# wander-compass-upside-down.net
KiCad netlist of a schematic drawn in EAGLE
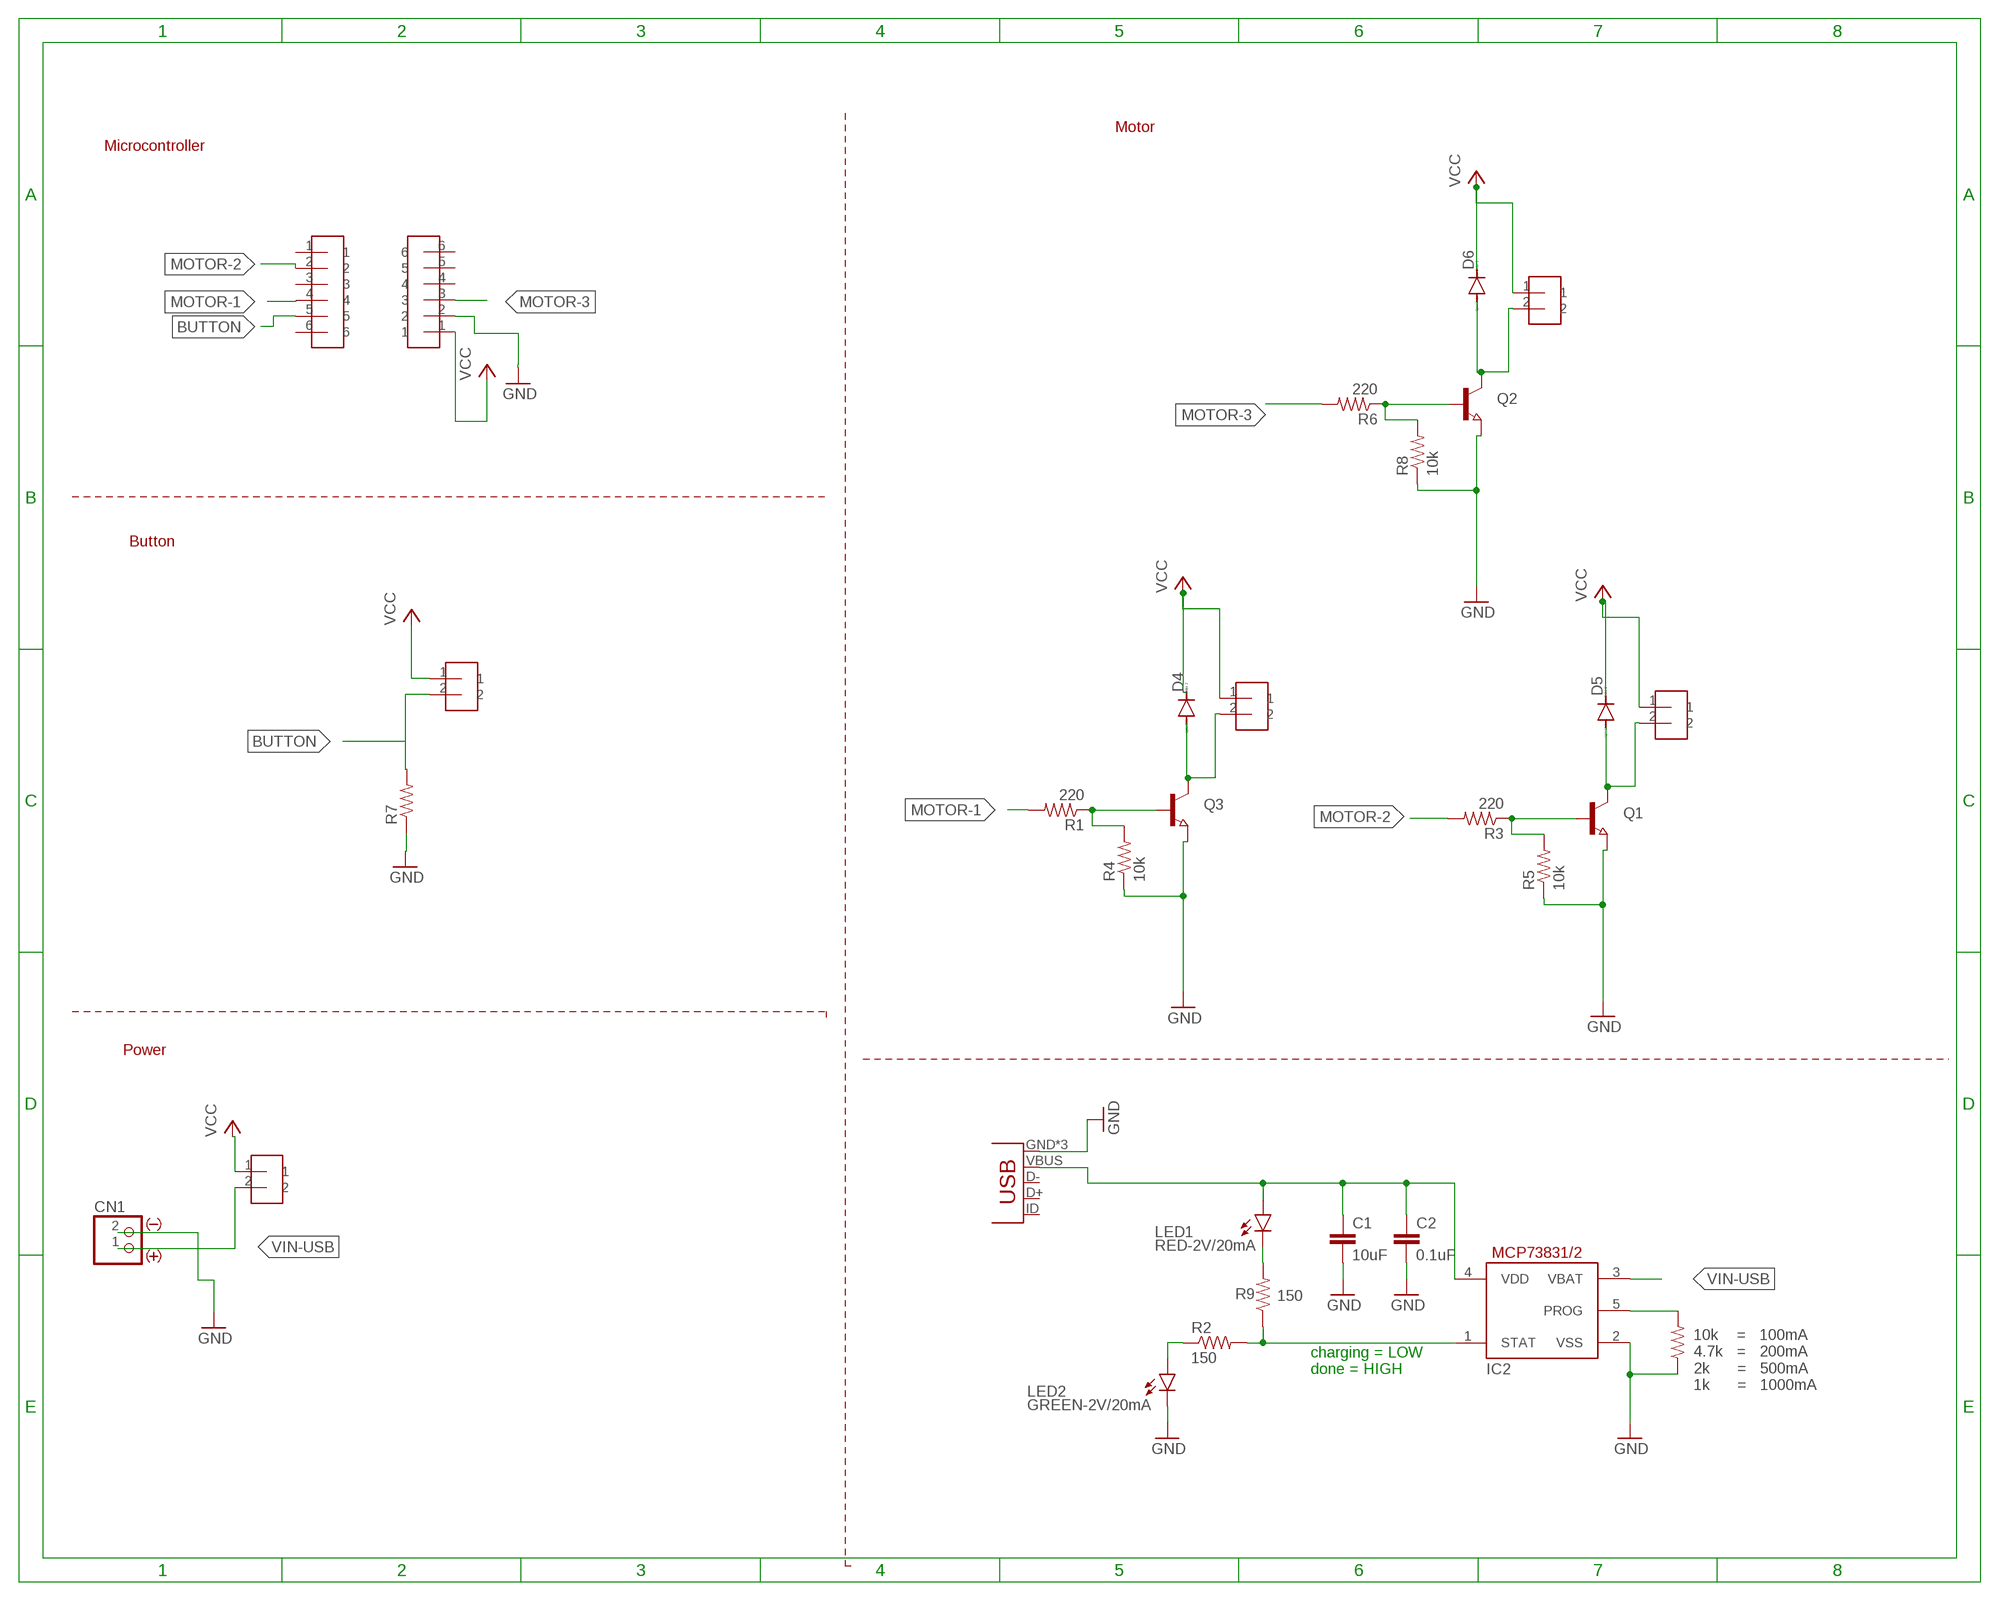
[diagram p0: schematic, sheet 1]

(export (version "E")
  (design (tool "Eeschema 10.0.6"))
  (components
    (comp (ref "C1")
      (value "10uF")
      (footprint "eagle-import:0805")
      (libsource (lib "eagle-import") (part "CAP-0805"))
    )
    (comp (ref "C2")
      (value "0.1uF")
      (footprint "eagle-import:0805")
      (libsource (lib "eagle-import") (part "CAP-0805"))
    )
    (comp (ref "CN1")
      (value "JST_2PIN_BATTERY-SMT-HORIZ")
      (footprint "eagle-import:JST-PH-2-SMT-RA")
      (libsource (lib "eagle-import") (part "JST_2PIN_BATTERY-SMT-HORIZ"))
    )
    (comp (ref "D4")
      (value "DIODE-SOD523")
      (footprint "eagle-import:SOD523")
      (libsource (lib "eagle-import") (part "DIODE-SOD523"))
    )
    (comp (ref "D5")
      (value "DIODE-SOD523")
      (footprint "eagle-import:SOD523")
      (libsource (lib "eagle-import") (part "DIODE-SOD523"))
    )
    (comp (ref "D6")
      (value "DIODE-SOD523")
      (footprint "eagle-import:SOD523")
      (libsource (lib "eagle-import") (part "DIODE-SOD523"))
    )
    (comp (ref "IC2")
      (value "LIPO_CHARGER/OT")
      (footprint "eagle-import:SOT23-5L")
      (libsource (lib "eagle-import") (part "LIPO_CHARGER/OT"))
    )
    (comp (ref "JP1")
      (value "USB_CONN-10118192-0001LF")
      (footprint "eagle-import:USB-MICROB")
      (libsource (lib "eagle-import") (part "USB_CONN-10118192-0001LF"))
    )
    (comp (ref "LED1")
      (value "RED-2V/20mA")
      (footprint "eagle-import:CHIP-LED0805")
      (libsource (lib "eagle-import") (part "LED-0805"))
    )
    (comp (ref "LED2")
      (value "GREEN-2V/20mA")
      (footprint "eagle-import:CHIP-LED0805")
      (libsource (lib "eagle-import") (part "LED-0805"))
    )
    (comp (ref "MOTOR-CENTER-HEADER")
      (value "HEADER-2")
      (footprint "eagle-import:HEADER-2")
      (libsource (lib "eagle-import") (part "HEADER-2"))
    )
    (comp (ref "MOTOR-RIGHT-HEADER")
      (value "HEADER-2")
      (footprint "eagle-import:HEADER-2")
      (libsource (lib "eagle-import") (part "HEADER-2"))
    )
    (comp (ref "MOTOR_LEFT_HEADER")
      (value "HEADER-2")
      (footprint "eagle-import:HEADER-2")
      (libsource (lib "eagle-import") (part "HEADER-2"))
    )
    (comp (ref "Q1")
      (value "TRANSISTOR-NPN-SOT23")
      (footprint "eagle-import:SOT23")
      (libsource (lib "eagle-import") (part "TRANSISTOR-NPN-SOT23"))
    )
    (comp (ref "Q2")
      (value "TRANSISTOR-NPN-SOT23")
      (footprint "eagle-import:SOT23")
      (libsource (lib "eagle-import") (part "TRANSISTOR-NPN-SOT23"))
    )
    (comp (ref "Q3")
      (value "TRANSISTOR-NPN-SOT23")
      (footprint "eagle-import:SOT23")
      (libsource (lib "eagle-import") (part "TRANSISTOR-NPN-SOT23"))
    )
    (comp (ref "R1")
      (value "220")
      (footprint "eagle-import:0603-RES")
      (libsource (lib "eagle-import") (part "RESISTOR0603"))
    )
    (comp (ref "R2")
      (value "150")
      (footprint "eagle-import:0805")
      (libsource (lib "eagle-import") (part "RESISTOR-0805"))
    )
    (comp (ref "R3")
      (value "220")
      (footprint "eagle-import:0603-RES")
      (libsource (lib "eagle-import") (part "RESISTOR0603"))
    )
    (comp (ref "R4")
      (value "10k")
      (footprint "eagle-import:0603-RES")
      (libsource (lib "eagle-import") (part "RESISTOR0603"))
    )
    (comp (ref "R5")
      (value "10k")
      (footprint "eagle-import:0603-RES")
      (libsource (lib "eagle-import") (part "RESISTOR0603"))
    )
    (comp (ref "R6")
      (value "220")
      (footprint "eagle-import:0603-RES")
      (libsource (lib "eagle-import") (part "RESISTOR0603"))
    )
    (comp (ref "R7")
      (value "RESISTOR0603")
      (footprint "eagle-import:0603-RES")
      (libsource (lib "eagle-import") (part "RESISTOR0603"))
    )
    (comp (ref "R8")
      (value "10k")
      (footprint "eagle-import:0603-RES")
      (libsource (lib "eagle-import") (part "RESISTOR0603"))
    )
    (comp (ref "R9")
      (value "150")
      (footprint "eagle-import:0805")
      (libsource (lib "eagle-import") (part "RESISTOR-0805"))
    )
    (comp (ref "R10")
      (value "2k")
      (footprint "eagle-import:0805")
      (libsource (lib "eagle-import") (part "RESISTOR-0805"))
    )
    (comp (ref "U$1")
      (value "HEADER-2")
      (footprint "eagle-import:HEADER-2")
      (libsource (lib "eagle-import") (part "HEADER-2"))
    )
    (comp (ref "U$5")
      (value "HEADER-6")
      (footprint "eagle-import:HEADER-6")
      (libsource (lib "eagle-import") (part "HEADER-6"))
    )
    (comp (ref "U$6")
      (value "HEADER-6")
      (footprint "eagle-import:HEADER-6")
      (libsource (lib "eagle-import") (part "HEADER-6"))
    )
    (comp (ref "U$7")
      (value "HEADER-2")
      (footprint "eagle-import:HEADER-2")
      (libsource (lib "eagle-import") (part "HEADER-2"))
    )
  )
  (nets
    (net (code "1") (name "BUTTON") (class "Default")
      (node (ref "R7") (pin "2") (pinfunction "2_2") (pintype "passive"))
      (node (ref "U$1") (pin "2") (pinfunction "2_2") (pintype "bidirectional"))
      (node (ref "U$6") (pin "5") (pinfunction "5_5") (pintype "bidirectional"))
    )
    (net (code "2") (name "GND") (class "Default")
      (node (ref "C1") (pin "2") (pinfunction "2_2") (pintype "passive"))
      (node (ref "C2") (pin "2") (pinfunction "2_2") (pintype "passive"))
      (node (ref "CN1") (pin "2") (pinfunction "1_2") (pintype "passive"))
      (node (ref "IC2") (pin "2") (pinfunction "VSS_2") (pintype "power_in"))
      (node (ref "JP1") (pin "GND") (pinfunction "GND_GND") (pintype "bidirectional"))
      (node (ref "JP1") (pin "MT1") (pinfunction "GND_MT1") (pintype "bidirectional"))
      (node (ref "JP1") (pin "MT2") (pinfunction "GND_MT2") (pintype "bidirectional"))
      (node (ref "LED2") (pin "C") (pinfunction "C_C") (pintype "passive"))
      (node (ref "Q1") (pin "2") (pinfunction "E_2") (pintype "passive"))
      (node (ref "Q2") (pin "2") (pinfunction "E_2") (pintype "passive"))
      (node (ref "Q3") (pin "2") (pinfunction "E_2") (pintype "passive"))
      (node (ref "R10") (pin "1") (pinfunction "1_1") (pintype "passive"))
      (node (ref "R4") (pin "1") (pinfunction "1_1") (pintype "passive"))
      (node (ref "R5") (pin "1") (pinfunction "1_1") (pintype "passive"))
      (node (ref "R7") (pin "1") (pinfunction "1_1") (pintype "passive"))
      (node (ref "R8") (pin "1") (pinfunction "1_1") (pintype "passive"))
      (node (ref "U$5") (pin "2") (pinfunction "2_2") (pintype "bidirectional"))
    )
    (net (code "3") (name "MOTOR-1") (class "Default")
      (node (ref "R1") (pin "2") (pinfunction "2_2") (pintype "passive"))
      (node (ref "U$6") (pin "4") (pinfunction "4_4") (pintype "bidirectional"))
    )
    (net (code "4") (name "MOTOR-2") (class "Default")
      (node (ref "R3") (pin "2") (pinfunction "2_2") (pintype "passive"))
      (node (ref "U$6") (pin "2") (pinfunction "2_2") (pintype "bidirectional"))
    )
    (net (code "5") (name "MOTOR-3") (class "Default")
      (node (ref "R6") (pin "2") (pinfunction "2_2") (pintype "passive"))
      (node (ref "U$5") (pin "3") (pinfunction "3_3") (pintype "bidirectional"))
    )
    (net (code "6") (name "Net-(IC2-PROG)") (class "Default")
      (node (ref "IC2") (pin "5") (pinfunction "PROG_5") (pintype "input"))
      (node (ref "R10") (pin "2") (pinfunction "2_2") (pintype "passive"))
    )
    (net (code "7") (name "Net-(IC2-STAT)") (class "Default")
      (node (ref "IC2") (pin "1") (pinfunction "STAT_1") (pintype "output"))
      (node (ref "R2") (pin "2") (pinfunction "2_2") (pintype "passive"))
      (node (ref "R9") (pin "1") (pinfunction "1_1") (pintype "passive"))
    )
    (net (code "8") (name "Net-(IC2-VDD)") (class "Default")
      (node (ref "C1") (pin "1") (pinfunction "1_1") (pintype "passive"))
      (node (ref "C2") (pin "1") (pinfunction "1_1") (pintype "passive"))
      (node (ref "IC2") (pin "4") (pinfunction "VDD_4") (pintype "power_in"))
      (node (ref "JP1") (pin "VBUS") (pinfunction "VBUS_VBUS") (pintype "bidirectional"))
      (node (ref "LED1") (pin "A") (pinfunction "A_A") (pintype "passive"))
    )
    (net (code "9") (name "Net-(LED1-PadC)") (class "Default")
      (node (ref "LED1") (pin "C") (pinfunction "C_C") (pintype "passive"))
      (node (ref "R9") (pin "2") (pinfunction "2_2") (pintype "passive"))
    )
    (net (code "10") (name "Net-(LED2-PadA)") (class "Default")
      (node (ref "LED2") (pin "A") (pinfunction "A_A") (pintype "passive"))
      (node (ref "R2") (pin "1") (pinfunction "1_1") (pintype "passive"))
    )
    (net (code "11") (name "Net-(Q1-B)") (class "Default")
      (node (ref "Q1") (pin "1") (pinfunction "B_1") (pintype "passive"))
      (node (ref "R3") (pin "1") (pinfunction "1_1") (pintype "passive"))
      (node (ref "R5") (pin "2") (pinfunction "2_2") (pintype "passive"))
    )
    (net (code "12") (name "Net-(Q1-C)") (class "Default")
      (node (ref "D5") (pin "A") (pinfunction "A_A") (pintype "passive"))
      (node (ref "MOTOR-CENTER-HEADER") (pin "2") (pinfunction "2_2") (pintype "bidirectional"))
      (node (ref "Q1") (pin "3") (pinfunction "C_3") (pintype "passive"))
    )
    (net (code "13") (name "Net-(Q2-B)") (class "Default")
      (node (ref "Q2") (pin "1") (pinfunction "B_1") (pintype "passive"))
      (node (ref "R6") (pin "1") (pinfunction "1_1") (pintype "passive"))
      (node (ref "R8") (pin "2") (pinfunction "2_2") (pintype "passive"))
    )
    (net (code "14") (name "Net-(Q2-C)") (class "Default")
      (node (ref "D6") (pin "A") (pinfunction "A_A") (pintype "passive"))
      (node (ref "MOTOR-RIGHT-HEADER") (pin "2") (pinfunction "2_2") (pintype "bidirectional"))
      (node (ref "Q2") (pin "3") (pinfunction "C_3") (pintype "passive"))
    )
    (net (code "15") (name "Net-(Q3-B)") (class "Default")
      (node (ref "Q3") (pin "1") (pinfunction "B_1") (pintype "passive"))
      (node (ref "R1") (pin "1") (pinfunction "1_1") (pintype "passive"))
      (node (ref "R4") (pin "2") (pinfunction "2_2") (pintype "passive"))
    )
    (net (code "16") (name "Net-(Q3-C)") (class "Default")
      (node (ref "D4") (pin "A") (pinfunction "A_A") (pintype "passive"))
      (node (ref "MOTOR_LEFT_HEADER") (pin "2") (pinfunction "2_2") (pintype "bidirectional"))
      (node (ref "Q3") (pin "3") (pinfunction "C_3") (pintype "passive"))
    )
    (net (code "17") (name "VCC") (class "Default")
      (node (ref "D4") (pin "C") (pinfunction "C_C") (pintype "passive"))
      (node (ref "D5") (pin "C") (pinfunction "C_C") (pintype "passive"))
      (node (ref "D6") (pin "C") (pinfunction "C_C") (pintype "passive"))
      (node (ref "MOTOR-CENTER-HEADER") (pin "1") (pinfunction "1_1") (pintype "bidirectional"))
      (node (ref "MOTOR-RIGHT-HEADER") (pin "1") (pinfunction "1_1") (pintype "bidirectional"))
      (node (ref "MOTOR_LEFT_HEADER") (pin "1") (pinfunction "1_1") (pintype "bidirectional"))
      (node (ref "U$1") (pin "1") (pinfunction "1_1") (pintype "bidirectional"))
      (node (ref "U$5") (pin "1") (pinfunction "1_1") (pintype "bidirectional"))
      (node (ref "U$7") (pin "1") (pinfunction "1_1") (pintype "bidirectional"))
    )
    (net (code "18") (name "VIN-USB") (class "Default")
      (node (ref "CN1") (pin "1") (pinfunction "2_1") (pintype "passive"))
      (node (ref "IC2") (pin "3") (pinfunction "VBAT_3") (pintype "bidirectional"))
      (node (ref "U$7") (pin "2") (pinfunction "2_2") (pintype "bidirectional"))
    )
    (net (code "19") (name "unconnected-(JP1-PadD+)") (class "Default")
      (node (ref "JP1") (pin "D+") (pinfunction "D+_D+") (pintype "bidirectional"))
    )
    (net (code "20") (name "unconnected-(JP1-PadD-)") (class "Default")
      (node (ref "JP1") (pin "D-") (pinfunction "D-_D-") (pintype "bidirectional"))
    )
    (net (code "21") (name "unconnected-(JP1-SHIELD-PadID)") (class "Default")
      (node (ref "JP1") (pin "ID") (pinfunction "SHIELD_ID") (pintype "bidirectional"))
    )
    (net (code "22") (name "unconnected-(U$5-Pad4)") (class "Default")
      (node (ref "U$5") (pin "4") (pinfunction "4_4") (pintype "bidirectional"))
    )
    (net (code "23") (name "unconnected-(U$5-Pad5)") (class "Default")
      (node (ref "U$5") (pin "5") (pinfunction "5_5") (pintype "bidirectional"))
    )
    (net (code "24") (name "unconnected-(U$5-Pad6)") (class "Default")
      (node (ref "U$5") (pin "6") (pinfunction "6_6") (pintype "bidirectional"))
    )
    (net (code "25") (name "unconnected-(U$6-Pad1)") (class "Default")
      (node (ref "U$6") (pin "1") (pinfunction "1_1") (pintype "bidirectional"))
    )
    (net (code "26") (name "unconnected-(U$6-Pad3)") (class "Default")
      (node (ref "U$6") (pin "3") (pinfunction "3_3") (pintype "bidirectional"))
    )
    (net (code "27") (name "unconnected-(U$6-Pad6)") (class "Default")
      (node (ref "U$6") (pin "6") (pinfunction "6_6") (pintype "bidirectional"))
    )
  )
)
